# InputsExtras.net
KiCad netlist of a schematic drawn in Altium Designer
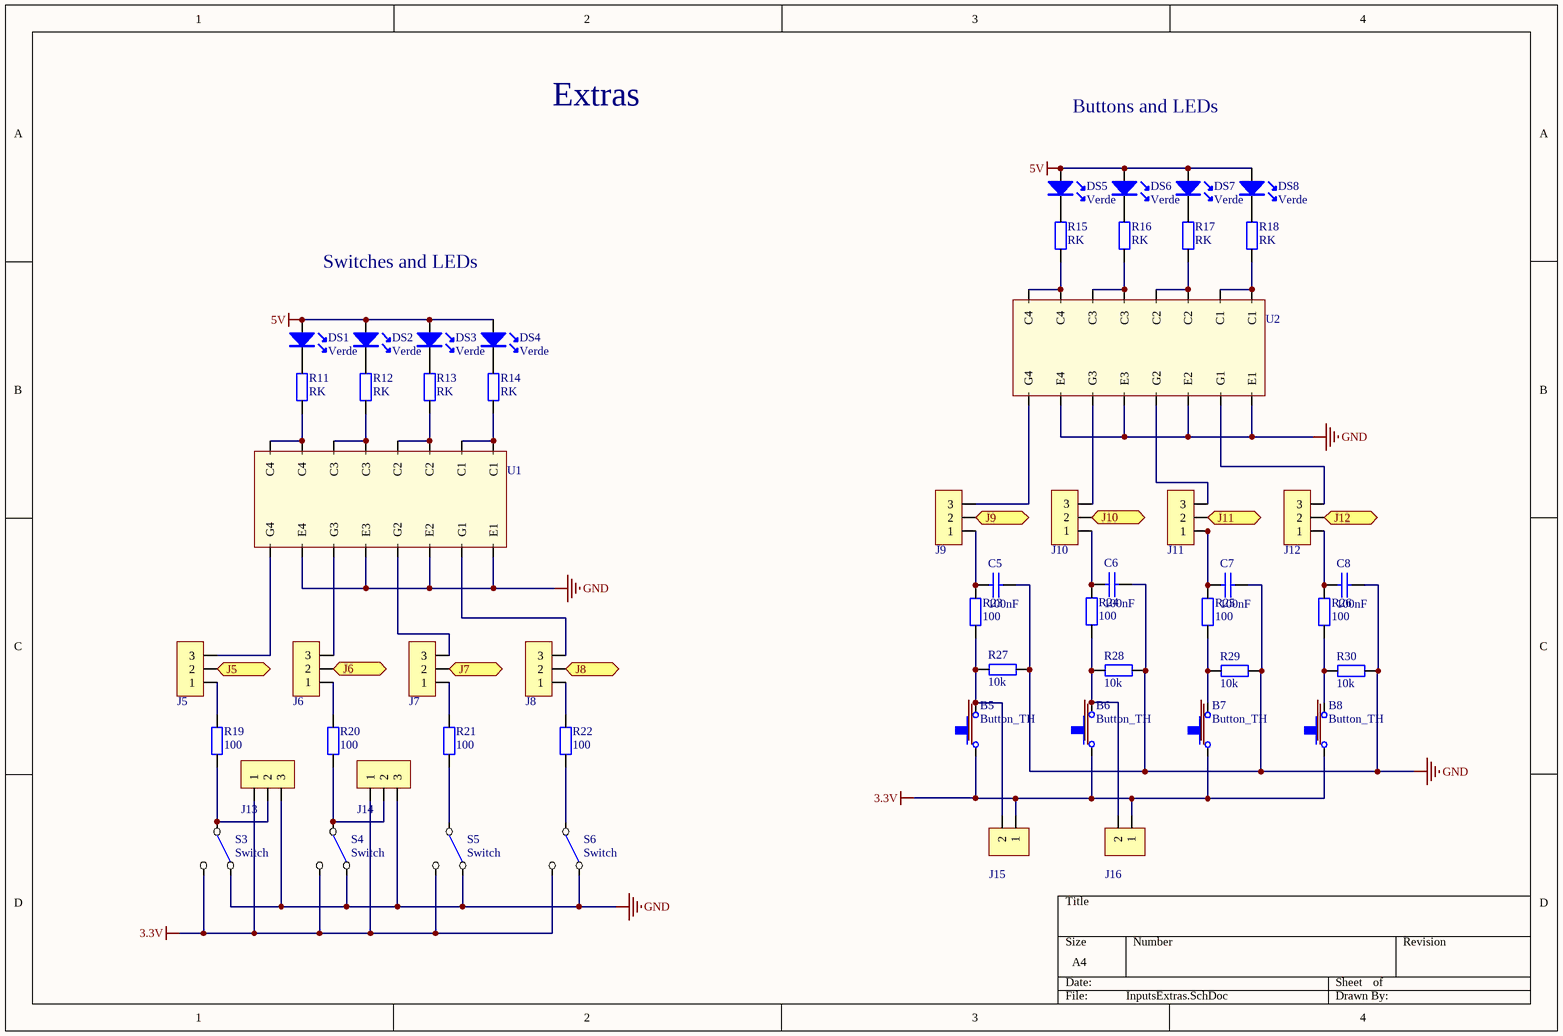
[diagram p0: InputsExtras.SchDoc]

(export (version "E")
  (design (tool "Eeschema 10.0.6"))
  (components
    (comp (ref "B5")
      (value "Button_TH")
      (footprint "ButtonTH")
      (libsource (lib "SCH_Lib") (part "Button_TH"))
    )
    (comp (ref "B6")
      (value "Button_TH")
      (footprint "ButtonTH")
      (libsource (lib "SCH_Lib") (part "Button_TH"))
    )
    (comp (ref "B7")
      (value "Button_TH")
      (footprint "ButtonTH")
      (libsource (lib "SCH_Lib") (part "Button_TH"))
    )
    (comp (ref "B8")
      (value "Button_TH")
      (footprint "ButtonTH")
      (libsource (lib "SCH_Lib") (part "Button_TH"))
    )
    (comp (ref "C5")
      (value "100nF")
      (footprint "1206")
      (description "Condensador")
      (libsource (lib "SCH_Lib") (part "Condensador"))
    )
    (comp (ref "C6")
      (value "100nF")
      (footprint "1206")
      (description "Condensador")
      (libsource (lib "SCH_Lib") (part "Condensador"))
    )
    (comp (ref "C7")
      (value "100nF")
      (footprint "1206")
      (description "Condensador")
      (libsource (lib "SCH_Lib") (part "Condensador"))
    )
    (comp (ref "C8")
      (value "100nF")
      (footprint "1206")
      (description "Condensador")
      (libsource (lib "SCH_Lib") (part "Condensador"))
    )
    (comp (ref "DS1") (value "Verde") (footprint "LED_100mil") (libsource (lib "SCH_Lib") (part "Led")))
    (comp (ref "DS2") (value "Verde") (footprint "LED_100mil") (libsource (lib "SCH_Lib") (part "Led")))
    (comp (ref "DS3") (value "Verde") (footprint "LED_100mil") (libsource (lib "SCH_Lib") (part "Led")))
    (comp (ref "DS4") (value "Verde") (footprint "LED_100mil") (libsource (lib "SCH_Lib") (part "Led")))
    (comp (ref "DS5") (value "Verde") (footprint "LED_100mil") (libsource (lib "SCH_Lib") (part "Led")))
    (comp (ref "DS6") (value "Verde") (footprint "LED_100mil") (libsource (lib "SCH_Lib") (part "Led")))
    (comp (ref "DS7") (value "Verde") (footprint "LED_100mil") (libsource (lib "SCH_Lib") (part "Led")))
    (comp (ref "DS8") (value "Verde") (footprint "LED_100mil") (libsource (lib "SCH_Lib") (part "Led")))
    (comp (ref "J5")
      (value "Cleva 2 vias")
      (footprint "con_3_100milis")
      (libsource (lib "SCH_Lib") (part "Con_3"))
    )
    (comp (ref "J6")
      (value "Cleva 2 vias")
      (footprint "con_3_100milis")
      (libsource (lib "SCH_Lib") (part "Con_3"))
    )
    (comp (ref "J7")
      (value "Cleva 2 vias")
      (footprint "con_3_100milis")
      (libsource (lib "SCH_Lib") (part "Con_3"))
    )
    (comp (ref "J8")
      (value "Cleva 2 vias")
      (footprint "con_3_100milis")
      (libsource (lib "SCH_Lib") (part "Con_3"))
    )
    (comp (ref "J9")
      (value "Cleva 2 vias")
      (footprint "con_3_100milis")
      (libsource (lib "SCH_Lib") (part "Con_3"))
    )
    (comp (ref "J10")
      (value "Cleva 2 vias")
      (footprint "con_3_100milis")
      (libsource (lib "SCH_Lib") (part "Con_3"))
    )
    (comp (ref "J11")
      (value "Cleva 2 vias")
      (footprint "con_3_100milis")
      (libsource (lib "SCH_Lib") (part "Con_3"))
    )
    (comp (ref "J12")
      (value "Cleva 2 vias")
      (footprint "con_3_100milis")
      (libsource (lib "SCH_Lib") (part "Con_3"))
    )
    (comp (ref "J13") (value "Cleva 2 vias") (footprint "Con3_KK_256") (libsource (lib "") (part "Con_3_1")))
    (comp (ref "J14") (value "Cleva 2 vias") (footprint "Con3_KK_256") (libsource (lib "") (part "Con_3_1")))
    (comp (ref "J15")
      (value "Cleva 2 vias")
      (footprint "Con2_KK_256")
      (libsource (lib "SCH_Lib") (part "Con_2"))
    )
    (comp (ref "J16")
      (value "Cleva 2 vias")
      (footprint "Con2_KK_256")
      (libsource (lib "SCH_Lib") (part "Con_2"))
    )
    (comp (ref "R11")
      (value "RK")
      (footprint "1206")
      (description "Resistencia")
      (libsource (lib "SCH_Lib") (part "Resistencia"))
    )
    (comp (ref "R12")
      (value "RK")
      (footprint "1206")
      (description "Resistencia")
      (libsource (lib "SCH_Lib") (part "Resistencia"))
    )
    (comp (ref "R13")
      (value "RK")
      (footprint "1206")
      (description "Resistencia")
      (libsource (lib "SCH_Lib") (part "Resistencia"))
    )
    (comp (ref "R14")
      (value "RK")
      (footprint "1206")
      (description "Resistencia")
      (libsource (lib "SCH_Lib") (part "Resistencia"))
    )
    (comp (ref "R15")
      (value "RK")
      (footprint "1206")
      (description "Resistencia")
      (libsource (lib "SCH_Lib") (part "Resistencia"))
    )
    (comp (ref "R16")
      (value "RK")
      (footprint "1206")
      (description "Resistencia")
      (libsource (lib "SCH_Lib") (part "Resistencia"))
    )
    (comp (ref "R17")
      (value "RK")
      (footprint "1206")
      (description "Resistencia")
      (libsource (lib "SCH_Lib") (part "Resistencia"))
    )
    (comp (ref "R18")
      (value "RK")
      (footprint "1206")
      (description "Resistencia")
      (libsource (lib "SCH_Lib") (part "Resistencia"))
    )
    (comp (ref "R19")
      (value "100")
      (footprint "1206")
      (description "Resistencia")
      (libsource (lib "SCH_Lib") (part "Resistencia"))
    )
    (comp (ref "R20")
      (value "100")
      (footprint "1206")
      (description "Resistencia")
      (libsource (lib "SCH_Lib") (part "Resistencia"))
    )
    (comp (ref "R21")
      (value "100")
      (footprint "1206")
      (description "Resistencia")
      (libsource (lib "SCH_Lib") (part "Resistencia"))
    )
    (comp (ref "R22")
      (value "100")
      (footprint "1206")
      (description "Resistencia")
      (libsource (lib "SCH_Lib") (part "Resistencia"))
    )
    (comp (ref "R23")
      (value "100")
      (footprint "1206")
      (description "Resistencia")
      (libsource (lib "SCH_Lib") (part "Resistencia"))
    )
    (comp (ref "R24")
      (value "100")
      (footprint "1206")
      (description "Resistencia")
      (libsource (lib "SCH_Lib") (part "Resistencia"))
    )
    (comp (ref "R25")
      (value "100")
      (footprint "1206")
      (description "Resistencia")
      (libsource (lib "SCH_Lib") (part "Resistencia"))
    )
    (comp (ref "R26")
      (value "100")
      (footprint "1206")
      (description "Resistencia")
      (libsource (lib "SCH_Lib") (part "Resistencia"))
    )
    (comp (ref "R27")
      (value "10k")
      (footprint "1206")
      (description "Resistencia")
      (libsource (lib "SCH_Lib") (part "Resistencia"))
    )
    (comp (ref "R28")
      (value "10k")
      (footprint "1206")
      (description "Resistencia")
      (libsource (lib "SCH_Lib") (part "Resistencia"))
    )
    (comp (ref "R29")
      (value "10k")
      (footprint "1206")
      (description "Resistencia")
      (libsource (lib "SCH_Lib") (part "Resistencia"))
    )
    (comp (ref "R30")
      (value "10k")
      (footprint "1206")
      (description "Resistencia")
      (libsource (lib "SCH_Lib") (part "Resistencia"))
    )
    (comp (ref "S3") (value "Switch") (footprint "SwitchTH_2Pos") (libsource (lib "SCH_Lib") (part "Switch")))
    (comp (ref "S4") (value "Switch") (footprint "SwitchTH_2Pos") (libsource (lib "SCH_Lib") (part "Switch")))
    (comp (ref "S5") (value "Switch") (footprint "SwitchTH_2Pos") (libsource (lib "SCH_Lib") (part "Switch")))
    (comp (ref "S6") (value "Switch") (footprint "SwitchTH_2Pos") (libsource (lib "SCH_Lib") (part "Switch")))
    (comp (ref "U1") (value "MMPQ3904") (footprint "SO-16") (libsource (lib "SCH_Lib") (part "MMPQ3904")))
    (comp (ref "U2") (value "MMPQ3904") (footprint "SO-16") (libsource (lib "SCH_Lib") (part "MMPQ3904")))
  )
  (nets
    (net (code "1") (name "/J5") (class "Default")
      (node (ref "J5") (pin "2") (pinfunction "2_2") (pintype "passive"))
    )
    (net (code "2") (name "/J6") (class "Default")
      (node (ref "J6") (pin "2") (pinfunction "2_2") (pintype "passive"))
    )
    (net (code "3") (name "/J7") (class "Default")
      (node (ref "J7") (pin "2") (pinfunction "2_2") (pintype "passive"))
    )
    (net (code "4") (name "/J8") (class "Default")
      (node (ref "J8") (pin "2") (pinfunction "2_2") (pintype "passive"))
    )
    (net (code "5") (name "/J9") (class "Default")
      (node (ref "J9") (pin "2") (pinfunction "2_2") (pintype "passive"))
    )
    (net (code "6") (name "/J10") (class "Default")
      (node (ref "J10") (pin "2") (pinfunction "2_2") (pintype "passive"))
    )
    (net (code "7") (name "/J11") (class "Default")
      (node (ref "J11") (pin "2") (pinfunction "2_2") (pintype "passive"))
    )
    (net (code "8") (name "/J12") (class "Default")
      (node (ref "J12") (pin "2") (pinfunction "2_2") (pintype "passive"))
    )
    (net (code "9") (name "3.3V") (class "Default")
      (node (ref "B5") (pin "1") (pinfunction "1_1") (pintype "passive"))
      (node (ref "B6") (pin "1") (pinfunction "1_1") (pintype "passive"))
      (node (ref "B7") (pin "1") (pinfunction "1_1") (pintype "passive"))
      (node (ref "B8") (pin "1") (pinfunction "1_1") (pintype "passive"))
      (node (ref "J13") (pin "1") (pinfunction "1_1") (pintype "passive"))
      (node (ref "J14") (pin "1") (pinfunction "1_1") (pintype "passive"))
      (node (ref "J15") (pin "1") (pinfunction "1_1") (pintype "passive"))
      (node (ref "J16") (pin "1") (pinfunction "1_1") (pintype "passive"))
      (node (ref "S3") (pin "2") (pinfunction "ON2_2") (pintype "passive"))
      (node (ref "S4") (pin "2") (pinfunction "ON2_2") (pintype "passive"))
      (node (ref "S5") (pin "2") (pinfunction "ON2_2") (pintype "passive"))
      (node (ref "S6") (pin "2") (pinfunction "ON2_2") (pintype "passive"))
    )
    (net (code "10") (name "5V") (class "Default")
      (node (ref "DS1") (pin "A") (pinfunction "A_A") (pintype "passive"))
      (node (ref "DS2") (pin "A") (pinfunction "A_A") (pintype "passive"))
      (node (ref "DS3") (pin "A") (pinfunction "A_A") (pintype "passive"))
      (node (ref "DS4") (pin "A") (pinfunction "A_A") (pintype "passive"))
      (node (ref "DS5") (pin "A") (pinfunction "A_A") (pintype "passive"))
      (node (ref "DS6") (pin "A") (pinfunction "A_A") (pintype "passive"))
      (node (ref "DS7") (pin "A") (pinfunction "A_A") (pintype "passive"))
      (node (ref "DS8") (pin "A") (pinfunction "A_A") (pintype "passive"))
    )
    (net (code "11") (name "GND") (class "Default")
      (node (ref "C5") (pin "1") (pintype "passive"))
      (node (ref "C6") (pin "1") (pintype "passive"))
      (node (ref "C7") (pin "1") (pintype "passive"))
      (node (ref "C8") (pin "1") (pintype "passive"))
      (node (ref "J13") (pin "3") (pinfunction "3_3") (pintype "passive"))
      (node (ref "J14") (pin "3") (pinfunction "3_3") (pintype "passive"))
      (node (ref "R27") (pin "1") (pinfunction "1_1") (pintype "passive"))
      (node (ref "R28") (pin "1") (pinfunction "1_1") (pintype "passive"))
      (node (ref "R29") (pin "1") (pinfunction "1_1") (pintype "passive"))
      (node (ref "R30") (pin "1") (pinfunction "1_1") (pintype "passive"))
      (node (ref "S3") (pin "0") (pinfunction "ON1_0") (pintype "passive"))
      (node (ref "S4") (pin "0") (pinfunction "ON1_0") (pintype "passive"))
      (node (ref "S5") (pin "0") (pinfunction "ON1_0") (pintype "passive"))
      (node (ref "S6") (pin "0") (pinfunction "ON1_0") (pintype "passive"))
      (node (ref "U1") (pin "10") (pinfunction "E4_10") (pintype "passive"))
      (node (ref "U1") (pin "12") (pinfunction "E3_12") (pintype "passive"))
      (node (ref "U1") (pin "14") (pinfunction "E2_14") (pintype "passive"))
      (node (ref "U1") (pin "16") (pinfunction "E1_16") (pintype "passive"))
      (node (ref "U2") (pin "10") (pinfunction "E4_10") (pintype "passive"))
      (node (ref "U2") (pin "12") (pinfunction "E3_12") (pintype "passive"))
      (node (ref "U2") (pin "14") (pinfunction "E2_14") (pintype "passive"))
      (node (ref "U2") (pin "16") (pinfunction "E1_16") (pintype "passive"))
    )
    (net (code "12") (name "Net-(B5-Pad0)") (class "Default")
      (node (ref "B5") (pin "0") (pinfunction "0_0") (pintype "passive"))
      (node (ref "J15") (pin "2") (pinfunction "2_2") (pintype "passive"))
      (node (ref "R23") (pin "1") (pinfunction "1_1") (pintype "passive"))
      (node (ref "R27") (pin "2") (pinfunction "2_2") (pintype "passive"))
    )
    (net (code "13") (name "Net-(B6-Pad0)") (class "Default")
      (node (ref "B6") (pin "0") (pinfunction "0_0") (pintype "passive"))
      (node (ref "J16") (pin "2") (pinfunction "2_2") (pintype "passive"))
      (node (ref "R24") (pin "1") (pinfunction "1_1") (pintype "passive"))
      (node (ref "R28") (pin "2") (pinfunction "2_2") (pintype "passive"))
    )
    (net (code "14") (name "Net-(B7-Pad0)") (class "Default")
      (node (ref "B7") (pin "0") (pinfunction "0_0") (pintype "passive"))
      (node (ref "R25") (pin "1") (pinfunction "1_1") (pintype "passive"))
      (node (ref "R29") (pin "2") (pinfunction "2_2") (pintype "passive"))
    )
    (net (code "15") (name "Net-(B8-Pad0)") (class "Default")
      (node (ref "B8") (pin "0") (pinfunction "0_0") (pintype "passive"))
      (node (ref "R26") (pin "1") (pinfunction "1_1") (pintype "passive"))
      (node (ref "R30") (pin "2") (pinfunction "2_2") (pintype "passive"))
    )
    (net (code "16") (name "Net-(C5-Pad2)") (class "Default")
      (node (ref "C5") (pin "2") (pintype "passive"))
      (node (ref "J9") (pin "1") (pinfunction "1_1") (pintype "passive"))
      (node (ref "R23") (pin "2") (pinfunction "2_2") (pintype "passive"))
    )
    (net (code "17") (name "Net-(C6-Pad2)") (class "Default")
      (node (ref "C6") (pin "2") (pintype "passive"))
      (node (ref "J10") (pin "1") (pinfunction "1_1") (pintype "passive"))
      (node (ref "R24") (pin "2") (pinfunction "2_2") (pintype "passive"))
    )
    (net (code "18") (name "Net-(C7-Pad2)") (class "Default")
      (node (ref "C7") (pin "2") (pintype "passive"))
      (node (ref "J11") (pin "1") (pinfunction "1_1") (pintype "passive"))
      (node (ref "R25") (pin "2") (pinfunction "2_2") (pintype "passive"))
    )
    (net (code "19") (name "Net-(C8-Pad2)") (class "Default")
      (node (ref "C8") (pin "2") (pintype "passive"))
      (node (ref "J12") (pin "1") (pinfunction "1_1") (pintype "passive"))
      (node (ref "R26") (pin "2") (pinfunction "2_2") (pintype "passive"))
    )
    (net (code "20") (name "Net-(DS1-PadK)") (class "Default")
      (node (ref "DS1") (pin "K") (pinfunction "K_K") (pintype "passive"))
      (node (ref "R11") (pin "1") (pinfunction "1_1") (pintype "passive"))
    )
    (net (code "21") (name "Net-(DS2-PadK)") (class "Default")
      (node (ref "DS2") (pin "K") (pinfunction "K_K") (pintype "passive"))
      (node (ref "R12") (pin "1") (pinfunction "1_1") (pintype "passive"))
    )
    (net (code "22") (name "Net-(DS3-PadK)") (class "Default")
      (node (ref "DS3") (pin "K") (pinfunction "K_K") (pintype "passive"))
      (node (ref "R13") (pin "1") (pinfunction "1_1") (pintype "passive"))
    )
    (net (code "23") (name "Net-(DS4-PadK)") (class "Default")
      (node (ref "DS4") (pin "K") (pinfunction "K_K") (pintype "passive"))
      (node (ref "R14") (pin "1") (pinfunction "1_1") (pintype "passive"))
    )
    (net (code "24") (name "Net-(DS5-PadK)") (class "Default")
      (node (ref "DS5") (pin "K") (pinfunction "K_K") (pintype "passive"))
      (node (ref "R15") (pin "1") (pinfunction "1_1") (pintype "passive"))
    )
    (net (code "25") (name "Net-(DS6-PadK)") (class "Default")
      (node (ref "DS6") (pin "K") (pinfunction "K_K") (pintype "passive"))
      (node (ref "R16") (pin "1") (pinfunction "1_1") (pintype "passive"))
    )
    (net (code "26") (name "Net-(DS7-PadK)") (class "Default")
      (node (ref "DS7") (pin "K") (pinfunction "K_K") (pintype "passive"))
      (node (ref "R17") (pin "1") (pinfunction "1_1") (pintype "passive"))
    )
    (net (code "27") (name "Net-(DS8-PadK)") (class "Default")
      (node (ref "DS8") (pin "K") (pinfunction "K_K") (pintype "passive"))
      (node (ref "R18") (pin "1") (pinfunction "1_1") (pintype "passive"))
    )
    (net (code "28") (name "Net-(J5-Pad1)") (class "Default")
      (node (ref "J5") (pin "1") (pinfunction "1_1") (pintype "passive"))
      (node (ref "R19") (pin "2") (pinfunction "2_2") (pintype "passive"))
    )
    (net (code "29") (name "Net-(J6-Pad1)") (class "Default")
      (node (ref "J6") (pin "1") (pinfunction "1_1") (pintype "passive"))
      (node (ref "R20") (pin "2") (pinfunction "2_2") (pintype "passive"))
    )
    (net (code "30") (name "Net-(J7-Pad1)") (class "Default")
      (node (ref "J7") (pin "1") (pinfunction "1_1") (pintype "passive"))
      (node (ref "R21") (pin "2") (pinfunction "2_2") (pintype "passive"))
    )
    (net (code "31") (name "Net-(J8-Pad1)") (class "Default")
      (node (ref "J8") (pin "1") (pinfunction "1_1") (pintype "passive"))
      (node (ref "R22") (pin "2") (pinfunction "2_2") (pintype "passive"))
    )
    (net (code "32") (name "Net-(R11-Pad2)") (class "Default")
      (node (ref "R11") (pin "2") (pinfunction "2_2") (pintype "passive"))
      (node (ref "U1") (pin "7") (pinfunction "C4_7") (pintype "passive"))
      (node (ref "U1") (pin "8") (pinfunction "C4_8") (pintype "passive"))
    )
    (net (code "33") (name "Net-(R12-Pad2)") (class "Default")
      (node (ref "R12") (pin "2") (pinfunction "2_2") (pintype "passive"))
      (node (ref "U1") (pin "5") (pinfunction "C3_5") (pintype "passive"))
      (node (ref "U1") (pin "6") (pinfunction "C3_6") (pintype "passive"))
    )
    (net (code "34") (name "Net-(R13-Pad2)") (class "Default")
      (node (ref "R13") (pin "2") (pinfunction "2_2") (pintype "passive"))
      (node (ref "U1") (pin "3") (pinfunction "C2_3") (pintype "passive"))
      (node (ref "U1") (pin "4") (pinfunction "C2_4") (pintype "passive"))
    )
    (net (code "35") (name "Net-(R14-Pad2)") (class "Default")
      (node (ref "R14") (pin "2") (pinfunction "2_2") (pintype "passive"))
      (node (ref "U1") (pin "1") (pinfunction "C1_1") (pintype "passive"))
      (node (ref "U1") (pin "2") (pinfunction "C1_2") (pintype "passive"))
    )
    (net (code "36") (name "Net-(R15-Pad2)") (class "Default")
      (node (ref "R15") (pin "2") (pinfunction "2_2") (pintype "passive"))
      (node (ref "U2") (pin "7") (pinfunction "C4_7") (pintype "passive"))
      (node (ref "U2") (pin "8") (pinfunction "C4_8") (pintype "passive"))
    )
    (net (code "37") (name "Net-(R16-Pad2)") (class "Default")
      (node (ref "R16") (pin "2") (pinfunction "2_2") (pintype "passive"))
      (node (ref "U2") (pin "5") (pinfunction "C3_5") (pintype "passive"))
      (node (ref "U2") (pin "6") (pinfunction "C3_6") (pintype "passive"))
    )
    (net (code "38") (name "Net-(R17-Pad2)") (class "Default")
      (node (ref "R17") (pin "2") (pinfunction "2_2") (pintype "passive"))
      (node (ref "U2") (pin "3") (pinfunction "C2_3") (pintype "passive"))
      (node (ref "U2") (pin "4") (pinfunction "C2_4") (pintype "passive"))
    )
    (net (code "39") (name "Net-(R18-Pad2)") (class "Default")
      (node (ref "R18") (pin "2") (pinfunction "2_2") (pintype "passive"))
      (node (ref "U2") (pin "1") (pinfunction "C1_1") (pintype "passive"))
      (node (ref "U2") (pin "2") (pinfunction "C1_2") (pintype "passive"))
    )
    (net (code "40") (name "Net-(S3-COMMON)") (class "Default")
      (node (ref "J13") (pin "2") (pinfunction "2_2") (pintype "passive"))
      (node (ref "R19") (pin "1") (pinfunction "1_1") (pintype "passive"))
      (node (ref "S3") (pin "1") (pinfunction "COMMON_1") (pintype "passive"))
    )
    (net (code "41") (name "Net-(S4-COMMON)") (class "Default")
      (node (ref "J14") (pin "2") (pinfunction "2_2") (pintype "passive"))
      (node (ref "R20") (pin "1") (pinfunction "1_1") (pintype "passive"))
      (node (ref "S4") (pin "1") (pinfunction "COMMON_1") (pintype "passive"))
    )
    (net (code "42") (name "Net-(S5-COMMON)") (class "Default")
      (node (ref "R21") (pin "1") (pinfunction "1_1") (pintype "passive"))
      (node (ref "S5") (pin "1") (pinfunction "COMMON_1") (pintype "passive"))
    )
    (net (code "43") (name "Net-(S6-COMMON)") (class "Default")
      (node (ref "R22") (pin "1") (pinfunction "1_1") (pintype "passive"))
      (node (ref "S6") (pin "1") (pinfunction "COMMON_1") (pintype "passive"))
    )
    (net (code "44") (name "Net-(U1-G1)") (class "Default")
      (node (ref "J8") (pin "3") (pinfunction "3_3") (pintype "passive"))
      (node (ref "U1") (pin "15") (pinfunction "G1_15") (pintype "passive"))
    )
    (net (code "45") (name "Net-(U1-G2)") (class "Default")
      (node (ref "J7") (pin "3") (pinfunction "3_3") (pintype "passive"))
      (node (ref "U1") (pin "13") (pinfunction "G2_13") (pintype "passive"))
    )
    (net (code "46") (name "Net-(U1-G3)") (class "Default")
      (node (ref "J6") (pin "3") (pinfunction "3_3") (pintype "passive"))
      (node (ref "U1") (pin "11") (pinfunction "G3_11") (pintype "passive"))
    )
    (net (code "47") (name "Net-(U1-G4)") (class "Default")
      (node (ref "J5") (pin "3") (pinfunction "3_3") (pintype "passive"))
      (node (ref "U1") (pin "9") (pinfunction "G4_9") (pintype "passive"))
    )
    (net (code "48") (name "Net-(U2-G1)") (class "Default")
      (node (ref "J12") (pin "3") (pinfunction "3_3") (pintype "passive"))
      (node (ref "U2") (pin "15") (pinfunction "G1_15") (pintype "passive"))
    )
    (net (code "49") (name "Net-(U2-G2)") (class "Default")
      (node (ref "J11") (pin "3") (pinfunction "3_3") (pintype "passive"))
      (node (ref "U2") (pin "13") (pinfunction "G2_13") (pintype "passive"))
    )
    (net (code "50") (name "Net-(U2-G3)") (class "Default")
      (node (ref "J10") (pin "3") (pinfunction "3_3") (pintype "passive"))
      (node (ref "U2") (pin "11") (pinfunction "G3_11") (pintype "passive"))
    )
    (net (code "51") (name "Net-(U2-G4)") (class "Default")
      (node (ref "J9") (pin "3") (pinfunction "3_3") (pintype "passive"))
      (node (ref "U2") (pin "9") (pinfunction "G4_9") (pintype "passive"))
    )
  )
)
